# Connector.net
KiCad netlist of a schematic drawn in Altium Designer
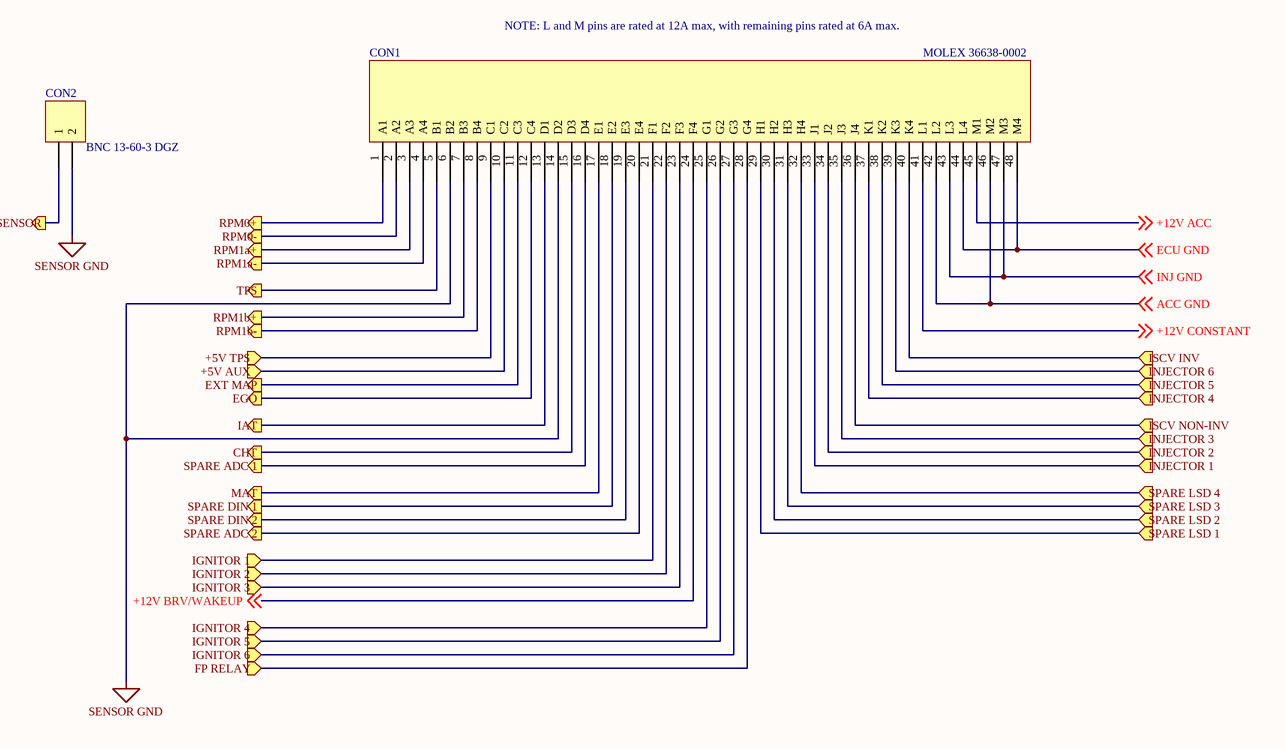
[diagram p0: Connector.SchDoc]

(export (version "E")
  (design (tool "Eeschema 10.0.6"))
  (components
    (comp (ref "CON1")
      (value "MOLEX 36638-0002")
      (libsource (lib "FreeEMS Schematic Library") (part "MOLEX 36638-0002"))
    )
    (comp (ref "CON2")
      (value "BNC 13-60-3 DGZ")
      (footprint "HDR1X2")
      (description "Header, 2-Pin")
      (fields (field (name "PUBLISHER") "Altium Limited"))
      (libsource (lib "Miscellaneous Connectors") (part "Header 2"))
    )
  )
  (nets
    (net (code "1") (name "+12V ACC") (class "Default")
      (node (ref "CON1") (pin "45") (pinfunction "M1_45") (pintype "passive"))
    )
    (net (code "2") (name "+12V BRV{slash}WAKEUP") (class "Default")
      (node (ref "CON1") (pin "24") (pinfunction "F4_24") (pintype "passive"))
    )
    (net (code "3") (name "+12V CONSTANT") (class "Default")
      (node (ref "CON1") (pin "41") (pinfunction "L1_41") (pintype "passive"))
    )
    (net (code "4") (name "/+5V AUX") (class "Default")
      (node (ref "CON1") (pin "10") (pinfunction "C2_10") (pintype "passive"))
    )
    (net (code "5") (name "/+5V TPS") (class "Default")
      (node (ref "CON1") (pin "9") (pinfunction "C1_9") (pintype "passive"))
    )
    (net (code "6") (name "/CHT") (class "Default")
      (node (ref "CON1") (pin "15") (pinfunction "D3_15") (pintype "passive"))
    )
    (net (code "7") (name "/EGO") (class "Default")
      (node (ref "CON1") (pin "12") (pinfunction "C4_12") (pintype "passive"))
    )
    (net (code "8") (name "/EXT MAP") (class "Default")
      (node (ref "CON1") (pin "11") (pinfunction "C3_11") (pintype "passive"))
    )
    (net (code "9") (name "/FP RELAY") (class "Default")
      (node (ref "CON1") (pin "28") (pinfunction "G4_28") (pintype "passive"))
    )
    (net (code "10") (name "/IAT") (class "Default")
      (node (ref "CON1") (pin "13") (pinfunction "D1_13") (pintype "passive"))
    )
    (net (code "11") (name "/IGNITOR 1") (class "Default")
      (node (ref "CON1") (pin "21") (pinfunction "F1_21") (pintype "passive"))
    )
    (net (code "12") (name "/IGNITOR 2") (class "Default")
      (node (ref "CON1") (pin "22") (pinfunction "F2_22") (pintype "passive"))
    )
    (net (code "13") (name "/IGNITOR 3") (class "Default")
      (node (ref "CON1") (pin "23") (pinfunction "F3_23") (pintype "passive"))
    )
    (net (code "14") (name "/IGNITOR 4") (class "Default")
      (node (ref "CON1") (pin "25") (pinfunction "G1_25") (pintype "passive"))
    )
    (net (code "15") (name "/IGNITOR 5") (class "Default")
      (node (ref "CON1") (pin "26") (pinfunction "G2_26") (pintype "passive"))
    )
    (net (code "16") (name "/IGNITOR 6") (class "Default")
      (node (ref "CON1") (pin "27") (pinfunction "G3_27") (pintype "passive"))
    )
    (net (code "17") (name "/INJECTOR 1") (class "Default")
      (node (ref "CON1") (pin "33") (pinfunction "J1_33") (pintype "passive"))
    )
    (net (code "18") (name "/INJECTOR 2") (class "Default")
      (node (ref "CON1") (pin "34") (pinfunction "J2_34") (pintype "passive"))
    )
    (net (code "19") (name "/INJECTOR 3") (class "Default")
      (node (ref "CON1") (pin "35") (pinfunction "J3_35") (pintype "passive"))
    )
    (net (code "20") (name "/INJECTOR 4") (class "Default")
      (node (ref "CON1") (pin "37") (pinfunction "K1_37") (pintype "passive"))
    )
    (net (code "21") (name "/INJECTOR 5") (class "Default")
      (node (ref "CON1") (pin "38") (pinfunction "K2_38") (pintype "passive"))
    )
    (net (code "22") (name "/INJECTOR 6") (class "Default")
      (node (ref "CON1") (pin "39") (pinfunction "K3_39") (pintype "passive"))
    )
    (net (code "23") (name "/ISCV INV") (class "Default")
      (node (ref "CON1") (pin "40") (pinfunction "K4_40") (pintype "passive"))
    )
    (net (code "24") (name "/ISCV NON-INV") (class "Default")
      (node (ref "CON1") (pin "36") (pinfunction "J4_36") (pintype "passive"))
    )
    (net (code "25") (name "/KNOCK SENSOR") (class "Default")
      (node (ref "CON2") (pin "1") (pinfunction "1_1") (pintype "passive"))
    )
    (net (code "26") (name "/MAT") (class "Default")
      (node (ref "CON1") (pin "17") (pinfunction "E1_17") (pintype "passive"))
    )
    (net (code "27") (name "/RPM0+") (class "Default")
      (node (ref "CON1") (pin "1") (pinfunction "A1_1") (pintype "passive"))
    )
    (net (code "28") (name "/RPM0-") (class "Default")
      (node (ref "CON1") (pin "2") (pinfunction "A2_2") (pintype "passive"))
    )
    (net (code "29") (name "/RPM1a+") (class "Default")
      (node (ref "CON1") (pin "3") (pinfunction "A3_3") (pintype "passive"))
    )
    (net (code "30") (name "/RPM1a-") (class "Default")
      (node (ref "CON1") (pin "4") (pinfunction "A4_4") (pintype "passive"))
    )
    (net (code "31") (name "/RPM1b+") (class "Default")
      (node (ref "CON1") (pin "7") (pinfunction "B3_7") (pintype "passive"))
    )
    (net (code "32") (name "/RPM1b-") (class "Default")
      (node (ref "CON1") (pin "8") (pinfunction "B4_8") (pintype "passive"))
    )
    (net (code "33") (name "/SPARE ADC 1") (class "Default")
      (node (ref "CON1") (pin "16") (pinfunction "D4_16") (pintype "passive"))
    )
    (net (code "34") (name "/SPARE ADC 2") (class "Default")
      (node (ref "CON1") (pin "20") (pinfunction "E4_20") (pintype "passive"))
    )
    (net (code "35") (name "/SPARE DIN 1") (class "Default")
      (node (ref "CON1") (pin "18") (pinfunction "E2_18") (pintype "passive"))
    )
    (net (code "36") (name "/SPARE DIN 2") (class "Default")
      (node (ref "CON1") (pin "19") (pinfunction "E3_19") (pintype "passive"))
    )
    (net (code "37") (name "/SPARE LSD 1") (class "Default")
      (node (ref "CON1") (pin "29") (pinfunction "H1_29") (pintype "passive"))
    )
    (net (code "38") (name "/SPARE LSD 2") (class "Default")
      (node (ref "CON1") (pin "30") (pinfunction "H2_30") (pintype "passive"))
    )
    (net (code "39") (name "/SPARE LSD 3") (class "Default")
      (node (ref "CON1") (pin "31") (pinfunction "H3_31") (pintype "passive"))
    )
    (net (code "40") (name "/SPARE LSD 4") (class "Default")
      (node (ref "CON1") (pin "32") (pinfunction "H4_32") (pintype "passive"))
    )
    (net (code "41") (name "/TPS") (class "Default")
      (node (ref "CON1") (pin "5") (pinfunction "B1_5") (pintype "passive"))
    )
    (net (code "42") (name "ACC GND") (class "Default")
      (node (ref "CON1") (pin "42") (pinfunction "L2_42") (pintype "passive"))
      (node (ref "CON1") (pin "46") (pinfunction "M2_46") (pintype "passive"))
    )
    (net (code "43") (name "ECU GND") (class "Default")
      (node (ref "CON1") (pin "44") (pinfunction "L4_44") (pintype "passive"))
      (node (ref "CON1") (pin "48") (pinfunction "M4_48") (pintype "passive"))
    )
    (net (code "44") (name "INJ GND") (class "Default")
      (node (ref "CON1") (pin "43") (pinfunction "L3_43") (pintype "passive"))
      (node (ref "CON1") (pin "47") (pinfunction "M3_47") (pintype "passive"))
    )
    (net (code "45") (name "SENSOR GND") (class "Default")
      (node (ref "CON1") (pin "14") (pinfunction "D2_14") (pintype "passive"))
      (node (ref "CON1") (pin "6") (pinfunction "B2_6") (pintype "passive"))
      (node (ref "CON2") (pin "2") (pinfunction "2_2") (pintype "passive"))
    )
  )
)
